# ironman.net
KiCad netlist of a schematic drawn in EasyEDA
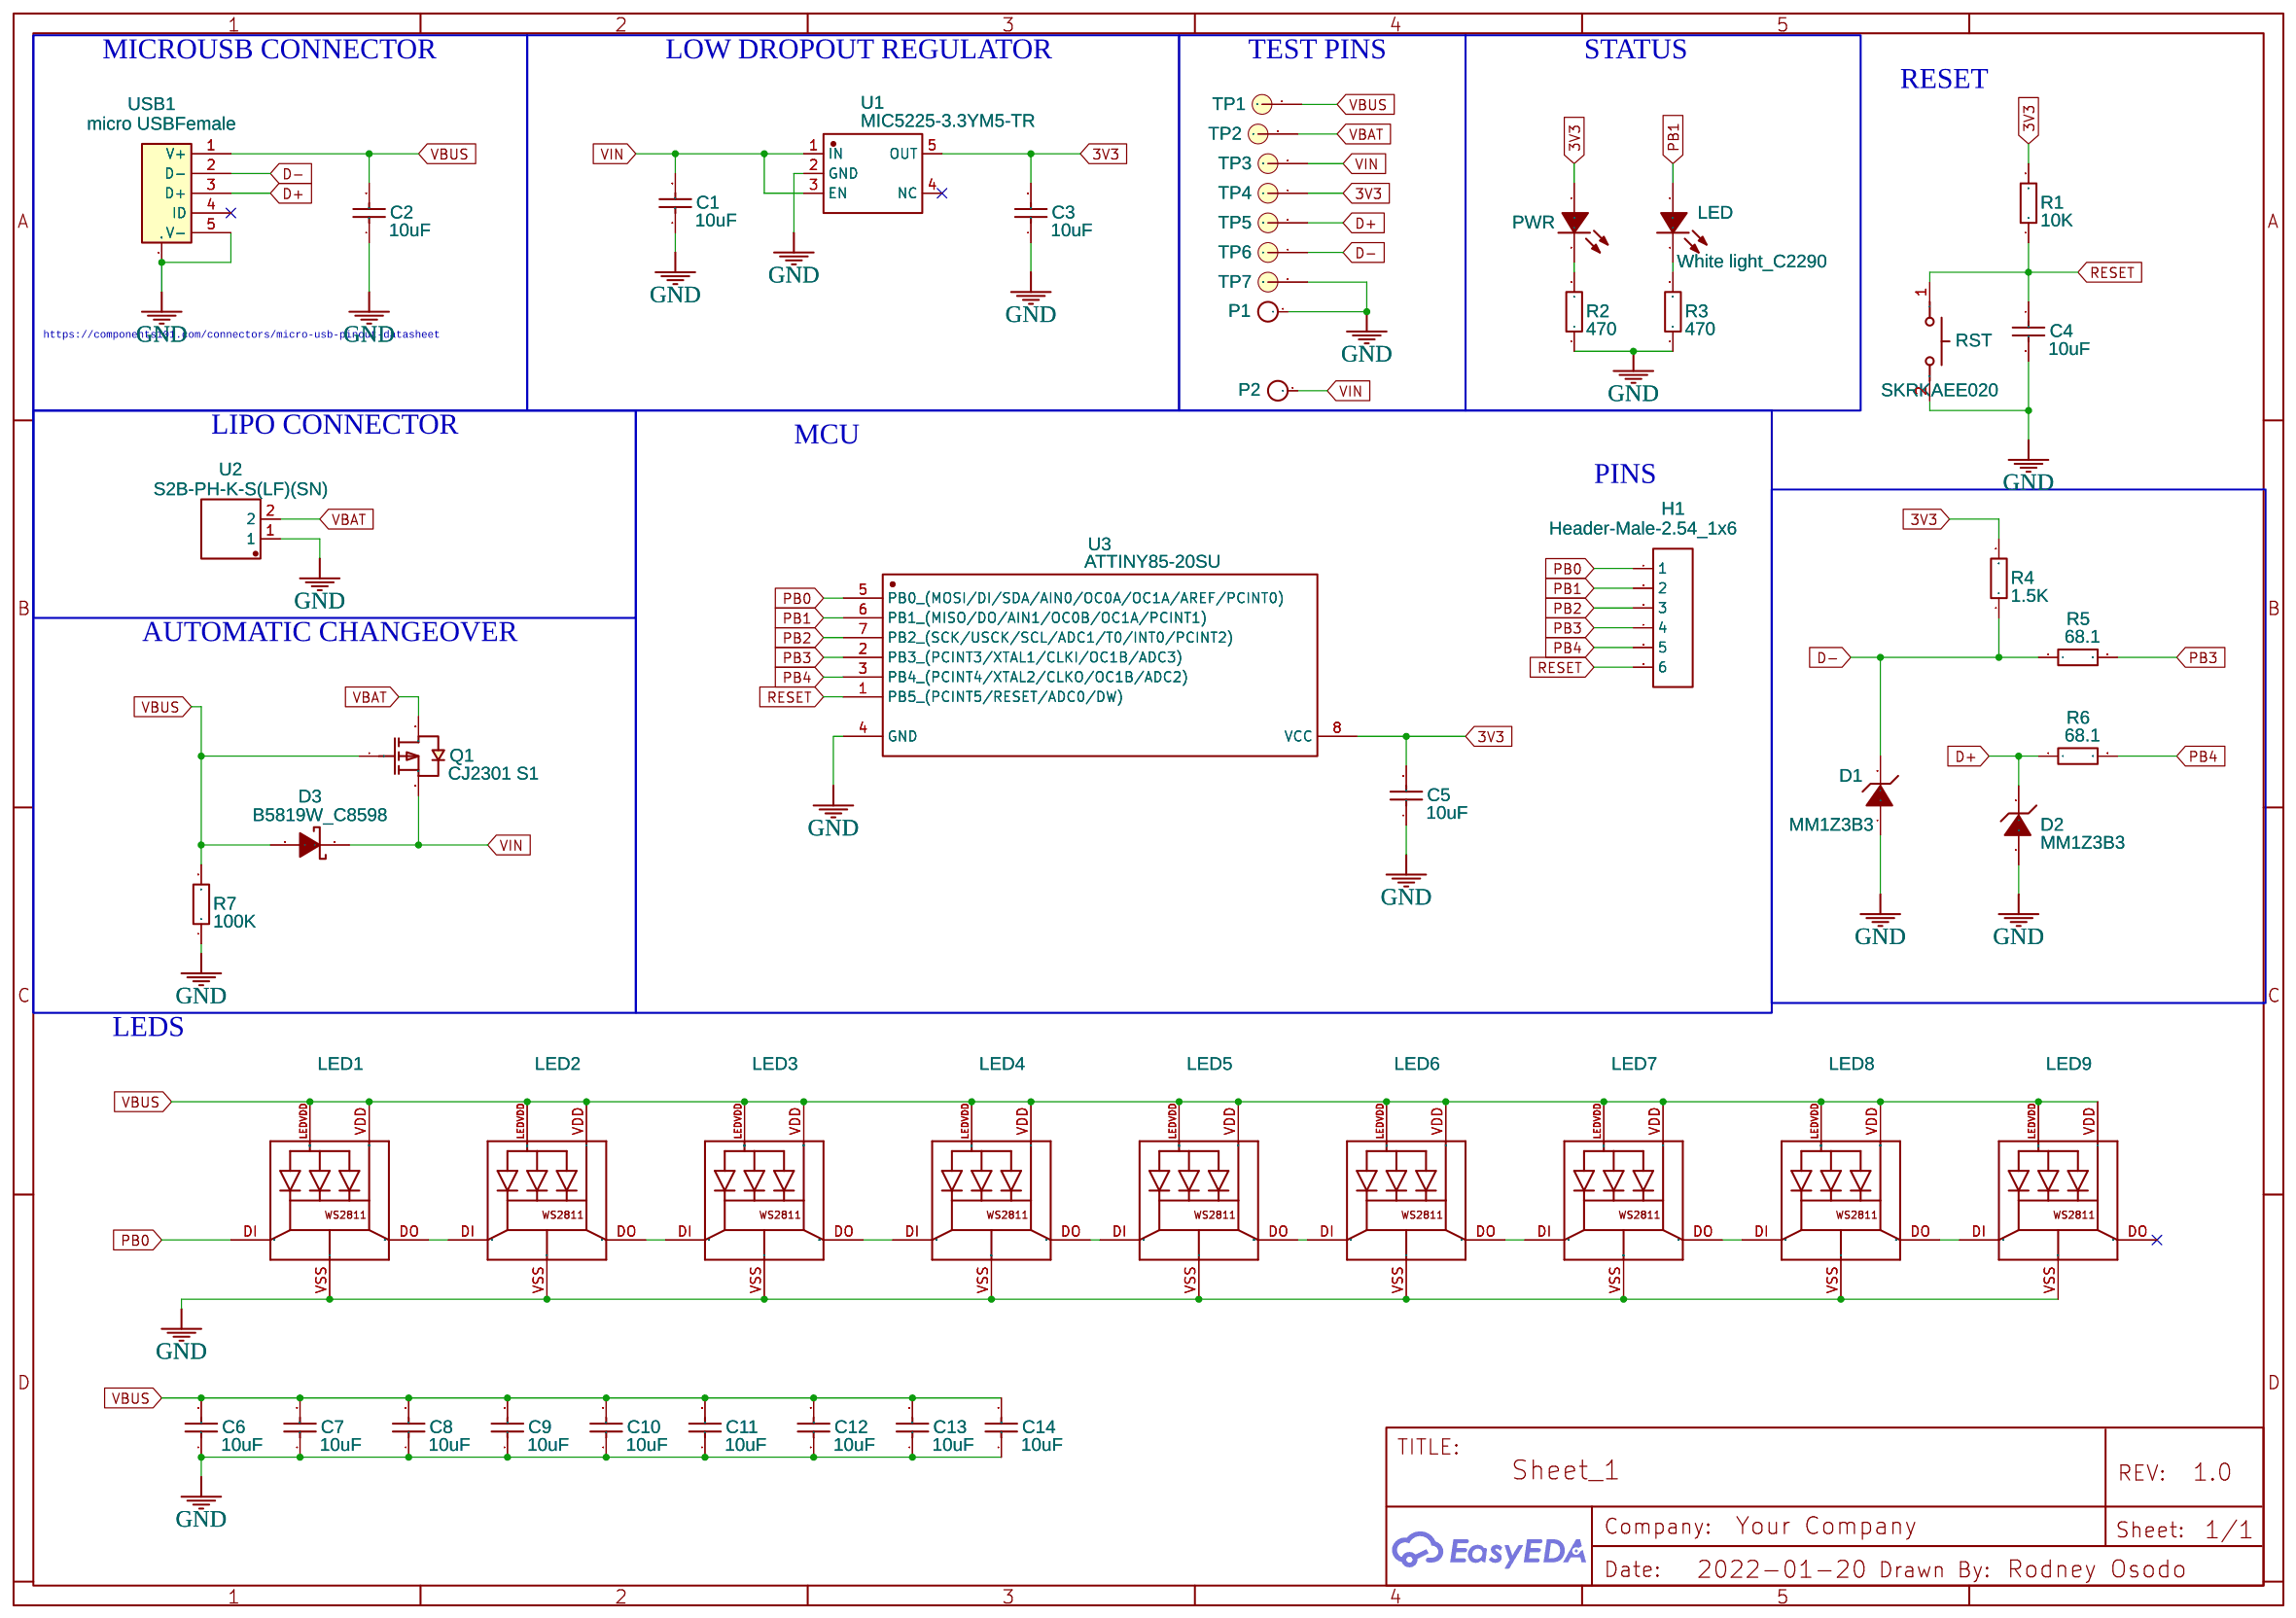
[diagram p0: schematic sheet]

(export (version "E")
  (design (tool "Eeschema 10.0.6"))
  (components
    (comp (ref "C1")
      (value "10uF")
      (fields
        (field (name "BOM_Manufacturer Part") "CL05A106MQ5NUNC")
        (field (name "BOM_Supplier Part") "C15525")
      )
      (libsource (lib "") (part "CL05A106MQ5NUNC"))
    )
    (comp (ref "C2")
      (value "10uF")
      (fields
        (field (name "BOM_Manufacturer Part") "CL05A106MQ5NUNC")
        (field (name "BOM_Supplier Part") "C15525")
      )
      (libsource (lib "") (part "CL05A106MQ5NUNC"))
    )
    (comp (ref "C3")
      (value "10uF")
      (fields
        (field (name "BOM_Manufacturer Part") "CL05A106MQ5NUNC")
        (field (name "BOM_Supplier Part") "C15525")
      )
      (libsource (lib "") (part "CL05A106MQ5NUNC"))
    )
    (comp (ref "C4")
      (value "10uF")
      (fields
        (field (name "BOM_Manufacturer Part") "CL05A106MQ5NUNC")
        (field (name "BOM_Supplier Part") "C15525")
      )
      (libsource (lib "") (part "CL05A106MQ5NUNC_1"))
    )
    (comp (ref "C5")
      (value "10uF")
      (fields
        (field (name "BOM_Manufacturer Part") "CL05A106MQ5NUNC")
        (field (name "BOM_Supplier Part") "C15525")
      )
      (libsource (lib "") (part "CL05A106MQ5NUNC"))
    )
    (comp (ref "C6")
      (value "10uF")
      (fields
        (field (name "BOM_Manufacturer Part") "CL05A106MQ5NUNC")
        (field (name "BOM_Supplier Part") "C15525")
      )
      (libsource (lib "") (part "CL05A106MQ5NUNC"))
    )
    (comp (ref "C7")
      (value "10uF")
      (fields
        (field (name "BOM_Manufacturer Part") "CL05A106MQ5NUNC")
        (field (name "BOM_Supplier Part") "C15525")
      )
      (libsource (lib "") (part "CL05A106MQ5NUNC"))
    )
    (comp (ref "C8")
      (value "10uF")
      (fields
        (field (name "BOM_Manufacturer Part") "CL05A106MQ5NUNC")
        (field (name "BOM_Supplier Part") "C15525")
      )
      (libsource (lib "") (part "CL05A106MQ5NUNC"))
    )
    (comp (ref "C9")
      (value "10uF")
      (fields
        (field (name "BOM_Manufacturer Part") "CL05A106MQ5NUNC")
        (field (name "BOM_Supplier Part") "C15525")
      )
      (libsource (lib "") (part "CL05A106MQ5NUNC"))
    )
    (comp (ref "C10")
      (value "10uF")
      (fields
        (field (name "BOM_Manufacturer Part") "CL05A106MQ5NUNC")
        (field (name "BOM_Supplier Part") "C15525")
      )
      (libsource (lib "") (part "CL05A106MQ5NUNC"))
    )
    (comp (ref "C11")
      (value "10uF")
      (fields
        (field (name "BOM_Manufacturer Part") "CL05A106MQ5NUNC")
        (field (name "BOM_Supplier Part") "C15525")
      )
      (libsource (lib "") (part "CL05A106MQ5NUNC"))
    )
    (comp (ref "C12")
      (value "10uF")
      (fields
        (field (name "BOM_Manufacturer Part") "CL05A106MQ5NUNC")
        (field (name "BOM_Supplier Part") "C15525")
      )
      (libsource (lib "") (part "CL05A106MQ5NUNC"))
    )
    (comp (ref "C13")
      (value "10uF")
      (fields
        (field (name "BOM_Manufacturer Part") "CL05A106MQ5NUNC")
        (field (name "BOM_Supplier Part") "C15525")
      )
      (libsource (lib "") (part "CL05A106MQ5NUNC"))
    )
    (comp (ref "C14")
      (value "10uF")
      (fields
        (field (name "BOM_Manufacturer Part") "CL05A106MQ5NUNC")
        (field (name "BOM_Supplier Part") "C15525")
      )
      (libsource (lib "") (part "CL05A106MQ5NUNC"))
    )
    (comp (ref "D1")
      (value "MM1Z3B3")
      (fields (field (name "BOM_Supplier Part") "C108453"))
      (libsource (lib "") (part "MM1Z3B3"))
    )
    (comp (ref "D2")
      (value "MM1Z3B3")
      (fields (field (name "BOM_Supplier Part") "C108453"))
      (libsource (lib "") (part "MM1Z3B3"))
    )
    (comp (ref "D3")
      (value "B5819W_C8598")
      (fields (field (name "BOM_Manufacturer Part") "B5819W") (field (name "BOM_Supplier Part") "C8598"))
      (libsource (lib "") (part "B5819W_C8598"))
    )
    (comp (ref "H1")
      (value "Header-Male-2.54_1x6")
      (fields (field (name "BOM_Supplier Part") "C37208"))
      (libsource (lib "") (part "Header-Male-2.54_1x6"))
    )
    (comp (ref "LED")
      (value "White light_C2290")
      (fields
        (field (name "BOM_Manufacturer Part") "0603White light")
        (field (name "BOM_Supplier Part") "C2290")
      )
      (libsource (lib "") (part "0603White light_C2290_1"))
    )
    (comp (ref "LED1") (value "WS28115050") (libsource (lib "") (part "WS28115050")))
    (comp (ref "LED2") (value "WS28115050") (libsource (lib "") (part "WS28115050")))
    (comp (ref "LED3") (value "WS28115050") (libsource (lib "") (part "WS28115050")))
    (comp (ref "LED4") (value "WS28115050") (libsource (lib "") (part "WS28115050")))
    (comp (ref "LED5") (value "WS28115050") (libsource (lib "") (part "WS28115050")))
    (comp (ref "LED6") (value "WS28115050") (libsource (lib "") (part "WS28115050")))
    (comp (ref "LED7") (value "WS28115050") (libsource (lib "") (part "WS28115050")))
    (comp (ref "LED8") (value "WS28115050") (libsource (lib "") (part "WS28115050")))
    (comp (ref "LED9") (value "WS28115050") (libsource (lib "") (part "WS28115050")))
    (comp (ref "P1") (value "3MMHOLE_PTH COPY") (libsource (lib "") (part "3MMHOLE_PTH COPY")))
    (comp (ref "P2") (value "3MMHOLE_PTH COPY") (libsource (lib "") (part "3MMHOLE_PTH COPY")))
    (comp (ref "PWR")
      (value "White light_C2290")
      (fields
        (field (name "BOM_Manufacturer Part") "0603White light")
        (field (name "BOM_Supplier Part") "C2290")
      )
      (libsource (lib "") (part "0603White light_C2290"))
    )
    (comp (ref "Q1")
      (value "CJ2301 S1")
      (fields (field (name "BOM_Supplier Part") "C8547"))
      (libsource (lib "") (part "CJ2301 S1"))
    )
    (comp (ref "R1")
      (value "10K")
      (fields
        (field (name "BOM_Manufacturer Part") "0603WAJ0103T5E")
        (field (name "BOM_Supplier Part") "C15401")
      )
      (libsource (lib "") (part "0603WAJ0103T5E"))
    )
    (comp (ref "R2")
      (value "470")
      (fields
        (field (name "BOM_Manufacturer Part") "0603WAF4700T5E")
        (field (name "BOM_Supplier Part") "C23179")
      )
      (libsource (lib "") (part "0603WAF4700T5E"))
    )
    (comp (ref "R3")
      (value "470")
      (fields
        (field (name "BOM_Manufacturer Part") "0603WAF4700T5E")
        (field (name "BOM_Supplier Part") "C23179")
      )
      (libsource (lib "") (part "0603WAF4700T5E"))
    )
    (comp (ref "R4")
      (value "1.5K")
      (fields
        (field (name "BOM_Manufacturer Part") "0603WAF1501T5E")
        (field (name "BOM_Supplier Part") "C22843")
      )
      (libsource (lib "") (part "0603WAF1501T5E"))
    )
    (comp (ref "R5")
      (value "68.1")
      (fields
        (field (name "BOM_Manufacturer Part") "0603WAF681JT5E")
        (field (name "BOM_Supplier Part") "C23097")
      )
      (libsource (lib "") (part "0603WAF681JT5E"))
    )
    (comp (ref "R6")
      (value "68.1")
      (fields
        (field (name "BOM_Manufacturer Part") "0603WAF681JT5E")
        (field (name "BOM_Supplier Part") "C23097")
      )
      (libsource (lib "") (part "0603WAF681JT5E"))
    )
    (comp (ref "R7")
      (value "100K")
      (fields
        (field (name "BOM_Manufacturer Part") "RC0603JR-07100KL")
        (field (name "BOM_Supplier Part") "C100048")
      )
      (libsource (lib "") (part "RC0603JR-07100KL"))
    )
    (comp (ref "RST")
      (value "SKRKAEE020")
      (fields (field (name "BOM_Supplier Part") "C115357"))
      (libsource (lib "") (part "SKRKAEE020"))
    )
    (comp (ref "TP1") (value "TEST PINS") (libsource (lib "") (part "TestPin")))
    (comp (ref "TP2") (value "TEST PINS") (libsource (lib "") (part "TestPin")))
    (comp (ref "TP3") (value "TEST PINS") (libsource (lib "") (part "TestPin")))
    (comp (ref "TP4") (value "TEST PINS") (libsource (lib "") (part "TestPin")))
    (comp (ref "TP5") (value "TEST PINS") (libsource (lib "") (part "TestPin")))
    (comp (ref "TP6") (value "TEST PINS") (libsource (lib "") (part "TestPin")))
    (comp (ref "TP7") (value "TEST PINS") (libsource (lib "") (part "TestPin")))
    (comp (ref "U1")
      (value "MIC5225-3.3YM5-TR")
      (fields (field (name "BOM_Supplier Part") "C512101"))
      (libsource (lib "") (part "MIC5225-3.3YM5-TR"))
    )
    (comp (ref "U2")
      (value "S2B-PH-K-S(LF)(SN)")
      (fields (field (name "BOM_Supplier Part") "C173752"))
      (libsource (lib "") (part "S2B-PH-K-S(LF)(SN)"))
    )
    (comp (ref "U3")
      (value "ATTINY85-20SU")
      (fields (field (name "BOM_Supplier Part") "C89852"))
      (libsource (lib "") (part "ATTINY85-20SU"))
    )
    (comp (ref "USB1")
      (value "micro USBFemale")
      (fields (field (name "BOM_Supplier Part") "C10418"))
      (libsource (lib "") (part "micro USBFemale"))
    )
  )
  (nets
    (net (code "1") (name "3V3") (class "Default")
      (node (ref "C3") (pin "2") (pinfunction "2_2") (pintype "input"))
      (node (ref "C5") (pin "2") (pinfunction "2_2") (pintype "input"))
      (node (ref "PWR") (pin "1") (pinfunction "A_1") (pintype "unspecified"))
      (node (ref "R1") (pin "2") (pinfunction "2_2") (pintype "input"))
      (node (ref "R4") (pin "2") (pinfunction "2_2") (pintype "input"))
      (node (ref "TP4") (pin "1") (pinfunction "1_1") (pintype "unspecified"))
      (node (ref "U1") (pin "5") (pinfunction "OUT_5") (pintype "unspecified"))
      (node (ref "U3") (pin "8") (pinfunction "VCC_8") (pintype "passive"))
    )
    (net (code "2") (name "D+") (class "Default")
      (node (ref "D2") (pin "2") (pinfunction "K_2") (pintype "unspecified"))
      (node (ref "R6") (pin "1") (pinfunction "1_1") (pintype "input"))
      (node (ref "TP5") (pin "1") (pinfunction "1_1") (pintype "unspecified"))
      (node (ref "USB1") (pin "3") (pinfunction "D+_3") (pintype "unspecified"))
    )
    (net (code "3") (name "D-") (class "Default")
      (node (ref "D1") (pin "2") (pinfunction "K_2") (pintype "unspecified"))
      (node (ref "R4") (pin "1") (pinfunction "1_1") (pintype "input"))
      (node (ref "R5") (pin "1") (pinfunction "1_1") (pintype "input"))
      (node (ref "TP6") (pin "1") (pinfunction "1_1") (pintype "unspecified"))
      (node (ref "USB1") (pin "2") (pinfunction "D-_2") (pintype "unspecified"))
    )
    (net (code "4") (name "GND") (class "Default")
      (node (ref "C1") (pin "1") (pinfunction "1_1") (pintype "input"))
      (node (ref "C10") (pin "1") (pinfunction "1_1") (pintype "input"))
      (node (ref "C11") (pin "1") (pinfunction "1_1") (pintype "input"))
      (node (ref "C12") (pin "1") (pinfunction "1_1") (pintype "input"))
      (node (ref "C13") (pin "1") (pinfunction "1_1") (pintype "input"))
      (node (ref "C14") (pin "1") (pinfunction "1_1") (pintype "input"))
      (node (ref "C2") (pin "1") (pinfunction "1_1") (pintype "input"))
      (node (ref "C3") (pin "1") (pinfunction "1_1") (pintype "input"))
      (node (ref "C4") (pin "2") (pinfunction "2_2") (pintype "input"))
      (node (ref "C5") (pin "1") (pinfunction "1_1") (pintype "input"))
      (node (ref "C6") (pin "1") (pinfunction "1_1") (pintype "input"))
      (node (ref "C7") (pin "1") (pinfunction "1_1") (pintype "input"))
      (node (ref "C8") (pin "1") (pinfunction "1_1") (pintype "input"))
      (node (ref "C9") (pin "1") (pinfunction "1_1") (pintype "input"))
      (node (ref "D1") (pin "1") (pinfunction "A_1") (pintype "unspecified"))
      (node (ref "D2") (pin "1") (pinfunction "A_1") (pintype "unspecified"))
      (node (ref "LED1") (pin "VSS") (pinfunction "GND_VSS") (pintype "bidirectional"))
      (node (ref "LED2") (pin "VSS") (pinfunction "GND_VSS") (pintype "bidirectional"))
      (node (ref "LED3") (pin "VSS") (pinfunction "GND_VSS") (pintype "bidirectional"))
      (node (ref "LED4") (pin "VSS") (pinfunction "GND_VSS") (pintype "bidirectional"))
      (node (ref "LED5") (pin "VSS") (pinfunction "GND_VSS") (pintype "bidirectional"))
      (node (ref "LED6") (pin "VSS") (pinfunction "GND_VSS") (pintype "bidirectional"))
      (node (ref "LED7") (pin "VSS") (pinfunction "GND_VSS") (pintype "bidirectional"))
      (node (ref "LED8") (pin "VSS") (pinfunction "GND_VSS") (pintype "bidirectional"))
      (node (ref "LED9") (pin "VSS") (pinfunction "GND_VSS") (pintype "bidirectional"))
      (node (ref "P1") (pin "1") (pinfunction "1_1") (pintype "unspecified"))
      (node (ref "R2") (pin "1") (pinfunction "1_1") (pintype "input"))
      (node (ref "R3") (pin "1") (pinfunction "1_1") (pintype "input"))
      (node (ref "R7") (pin "1") (pinfunction "1_1") (pintype "unspecified"))
      (node (ref "RST") (pin "2") (pinfunction "2_2") (pintype "unspecified"))
      (node (ref "TP7") (pin "1") (pinfunction "1_1") (pintype "unspecified"))
      (node (ref "U1") (pin "2") (pinfunction "GND_2") (pintype "unspecified"))
      (node (ref "U2") (pin "1") (pinfunction "1_1") (pintype "unspecified"))
      (node (ref "U3") (pin "4") (pinfunction "GND_4") (pintype "passive"))
      (node (ref "USB1") (pin "0") (pinfunction "MTN_0") (pintype "input"))
      (node (ref "USB1") (pin "5") (pinfunction "V-_5") (pintype "unspecified"))
    )
    (net (code "5") (name "Net-(LED-K)") (class "Default")
      (node (ref "LED") (pin "2") (pinfunction "K_2") (pintype "unspecified"))
      (node (ref "R3") (pin "2") (pinfunction "2_2") (pintype "input"))
    )
    (net (code "6") (name "Net-(LED1-PadDO)") (class "Default")
      (node (ref "LED1") (pin "DO") (pinfunction "DO_DO") (pintype "bidirectional"))
      (node (ref "LED2") (pin "DI") (pinfunction "DI_DI") (pintype "bidirectional"))
    )
    (net (code "7") (name "Net-(LED2-PadDO)") (class "Default")
      (node (ref "LED2") (pin "DO") (pinfunction "DO_DO") (pintype "bidirectional"))
      (node (ref "LED3") (pin "DI") (pinfunction "DI_DI") (pintype "bidirectional"))
    )
    (net (code "8") (name "Net-(LED3-PadDO)") (class "Default")
      (node (ref "LED3") (pin "DO") (pinfunction "DO_DO") (pintype "bidirectional"))
      (node (ref "LED4") (pin "DI") (pinfunction "DI_DI") (pintype "bidirectional"))
    )
    (net (code "9") (name "Net-(LED4-PadDO)") (class "Default")
      (node (ref "LED4") (pin "DO") (pinfunction "DO_DO") (pintype "bidirectional"))
      (node (ref "LED5") (pin "DI") (pinfunction "DI_DI") (pintype "bidirectional"))
    )
    (net (code "10") (name "Net-(LED5-PadDO)") (class "Default")
      (node (ref "LED5") (pin "DO") (pinfunction "DO_DO") (pintype "bidirectional"))
      (node (ref "LED6") (pin "DI") (pinfunction "DI_DI") (pintype "bidirectional"))
    )
    (net (code "11") (name "Net-(LED6-PadDO)") (class "Default")
      (node (ref "LED6") (pin "DO") (pinfunction "DO_DO") (pintype "bidirectional"))
      (node (ref "LED7") (pin "DI") (pinfunction "DI_DI") (pintype "bidirectional"))
    )
    (net (code "12") (name "Net-(LED7-PadDO)") (class "Default")
      (node (ref "LED7") (pin "DO") (pinfunction "DO_DO") (pintype "bidirectional"))
      (node (ref "LED8") (pin "DI") (pinfunction "DI_DI") (pintype "bidirectional"))
    )
    (net (code "13") (name "Net-(LED8-PadDO)") (class "Default")
      (node (ref "LED8") (pin "DO") (pinfunction "DO_DO") (pintype "bidirectional"))
      (node (ref "LED9") (pin "DI") (pinfunction "DI_DI") (pintype "bidirectional"))
    )
    (net (code "14") (name "Net-(PWR-K)") (class "Default")
      (node (ref "PWR") (pin "2") (pinfunction "K_2") (pintype "unspecified"))
      (node (ref "R2") (pin "2") (pinfunction "2_2") (pintype "input"))
    )
    (net (code "15") (name "PB0") (class "Default")
      (node (ref "H1") (pin "1") (pinfunction "1_1") (pintype "input"))
      (node (ref "LED1") (pin "DI") (pinfunction "DI_DI") (pintype "bidirectional"))
      (node (ref "U3") (pin "5") (pinfunction "PB0_(MOSI/DI/SDA/AIN0/OC0A/OC1A/AREF/PCINT0)_5") (pintype "bidirectional"))
    )
    (net (code "16") (name "PB1") (class "Default")
      (node (ref "H1") (pin "2") (pinfunction "2_2") (pintype "input"))
      (node (ref "LED") (pin "1") (pinfunction "A_1") (pintype "unspecified"))
      (node (ref "U3") (pin "6") (pinfunction "PB1_(MISO/DO/AIN1/OC0B/OC1A/PCINT1)_6") (pintype "bidirectional"))
    )
    (net (code "17") (name "PB2") (class "Default")
      (node (ref "H1") (pin "3") (pinfunction "3_3") (pintype "input"))
      (node (ref "U3") (pin "7") (pinfunction "PB2_(SCK/USCK/SCL/ADC1/T0/INT0/PCINT2)_7") (pintype "bidirectional"))
    )
    (net (code "18") (name "PB3") (class "Default")
      (node (ref "H1") (pin "4") (pinfunction "4_4") (pintype "input"))
      (node (ref "R5") (pin "2") (pinfunction "2_2") (pintype "input"))
      (node (ref "U3") (pin "2") (pinfunction "PB3_(PCINT3/XTAL1/CLKI/OC1B/ADC3)_2") (pintype "bidirectional"))
    )
    (net (code "19") (name "PB4") (class "Default")
      (node (ref "H1") (pin "5") (pinfunction "5_5") (pintype "input"))
      (node (ref "R6") (pin "2") (pinfunction "2_2") (pintype "input"))
      (node (ref "U3") (pin "3") (pinfunction "PB4_(PCINT4/XTAL2/CLKO/OC1B/ADC2)_3") (pintype "bidirectional"))
    )
    (net (code "20") (name "RESET") (class "Default")
      (node (ref "C4") (pin "1") (pinfunction "1_1") (pintype "input"))
      (node (ref "H1") (pin "6") (pinfunction "6_6") (pintype "input"))
      (node (ref "R1") (pin "1") (pinfunction "1_1") (pintype "input"))
      (node (ref "RST") (pin "1") (pinfunction "1_1") (pintype "unspecified"))
      (node (ref "U3") (pin "1") (pinfunction "PB5_(PCINT5/RESET/ADC0/DW)_1") (pintype "bidirectional"))
    )
    (net (code "21") (name "VBAT") (class "Default")
      (node (ref "Q1") (pin "3") (pinfunction "D_3") (pintype "unspecified"))
      (node (ref "TP2") (pin "1") (pinfunction "1_1") (pintype "unspecified"))
      (node (ref "U2") (pin "2") (pinfunction "2_2") (pintype "unspecified"))
    )
    (net (code "22") (name "VBUS") (class "Default")
      (node (ref "C10") (pin "2") (pinfunction "2_2") (pintype "input"))
      (node (ref "C11") (pin "2") (pinfunction "2_2") (pintype "input"))
      (node (ref "C12") (pin "2") (pinfunction "2_2") (pintype "input"))
      (node (ref "C13") (pin "2") (pinfunction "2_2") (pintype "input"))
      (node (ref "C14") (pin "2") (pinfunction "2_2") (pintype "input"))
      (node (ref "C2") (pin "2") (pinfunction "2_2") (pintype "input"))
      (node (ref "C6") (pin "2") (pinfunction "2_2") (pintype "input"))
      (node (ref "C7") (pin "2") (pinfunction "2_2") (pintype "input"))
      (node (ref "C8") (pin "2") (pinfunction "2_2") (pintype "input"))
      (node (ref "C9") (pin "2") (pinfunction "2_2") (pintype "input"))
      (node (ref "D3") (pin "2") (pinfunction "+_2") (pintype "unspecified"))
      (node (ref "LED1") (pin "LEDVDD") (pinfunction "LEDVDD_LEDVDD") (pintype "bidirectional"))
      (node (ref "LED1") (pin "VDD") (pinfunction "VDD_VDD") (pintype "bidirectional"))
      (node (ref "LED2") (pin "LEDVDD") (pinfunction "LEDVDD_LEDVDD") (pintype "bidirectional"))
      (node (ref "LED2") (pin "VDD") (pinfunction "VDD_VDD") (pintype "bidirectional"))
      (node (ref "LED3") (pin "LEDVDD") (pinfunction "LEDVDD_LEDVDD") (pintype "bidirectional"))
      (node (ref "LED3") (pin "VDD") (pinfunction "VDD_VDD") (pintype "bidirectional"))
      (node (ref "LED4") (pin "LEDVDD") (pinfunction "LEDVDD_LEDVDD") (pintype "bidirectional"))
      (node (ref "LED4") (pin "VDD") (pinfunction "VDD_VDD") (pintype "bidirectional"))
      (node (ref "LED5") (pin "LEDVDD") (pinfunction "LEDVDD_LEDVDD") (pintype "bidirectional"))
      (node (ref "LED5") (pin "VDD") (pinfunction "VDD_VDD") (pintype "bidirectional"))
      (node (ref "LED6") (pin "LEDVDD") (pinfunction "LEDVDD_LEDVDD") (pintype "bidirectional"))
      (node (ref "LED6") (pin "VDD") (pinfunction "VDD_VDD") (pintype "bidirectional"))
      (node (ref "LED7") (pin "LEDVDD") (pinfunction "LEDVDD_LEDVDD") (pintype "bidirectional"))
      (node (ref "LED7") (pin "VDD") (pinfunction "VDD_VDD") (pintype "bidirectional"))
      (node (ref "LED8") (pin "LEDVDD") (pinfunction "LEDVDD_LEDVDD") (pintype "bidirectional"))
      (node (ref "LED8") (pin "VDD") (pinfunction "VDD_VDD") (pintype "bidirectional"))
      (node (ref "LED9") (pin "LEDVDD") (pinfunction "LEDVDD_LEDVDD") (pintype "bidirectional"))
      (node (ref "LED9") (pin "VDD") (pinfunction "VDD_VDD") (pintype "bidirectional"))
      (node (ref "Q1") (pin "1") (pinfunction "G_1") (pintype "unspecified"))
      (node (ref "R7") (pin "2") (pinfunction "2_2") (pintype "unspecified"))
      (node (ref "TP1") (pin "1") (pinfunction "1_1") (pintype "unspecified"))
      (node (ref "USB1") (pin "1") (pinfunction "V+_1") (pintype "unspecified"))
    )
    (net (code "23") (name "VIN") (class "Default")
      (node (ref "C1") (pin "2") (pinfunction "2_2") (pintype "input"))
      (node (ref "D3") (pin "1") (pinfunction "-_1") (pintype "unspecified"))
      (node (ref "P2") (pin "1") (pinfunction "1_1") (pintype "unspecified"))
      (node (ref "Q1") (pin "2") (pinfunction "S_2") (pintype "unspecified"))
      (node (ref "TP3") (pin "1") (pinfunction "1_1") (pintype "unspecified"))
      (node (ref "U1") (pin "1") (pinfunction "IN_1") (pintype "unspecified"))
      (node (ref "U1") (pin "3") (pinfunction "EN_3") (pintype "unspecified"))
    )
    (net (code "24") (name "unconnected-(LED9-PadDO)") (class "Default")
      (node (ref "LED9") (pin "DO") (pinfunction "DO_DO") (pintype "bidirectional+no_connect"))
    )
    (net (code "25") (name "unconnected-(U1-NC-Pad4)") (class "Default")
      (node (ref "U1") (pin "4") (pinfunction "NC_4") (pintype "unspecified+no_connect"))
    )
    (net (code "26") (name "unconnected-(USB1-ID-Pad4)") (class "Default")
      (node (ref "USB1") (pin "4") (pinfunction "ID_4") (pintype "unspecified+no_connect"))
    )
  )
)
